# Main.net
KiCad netlist of a schematic drawn in Altium Designer
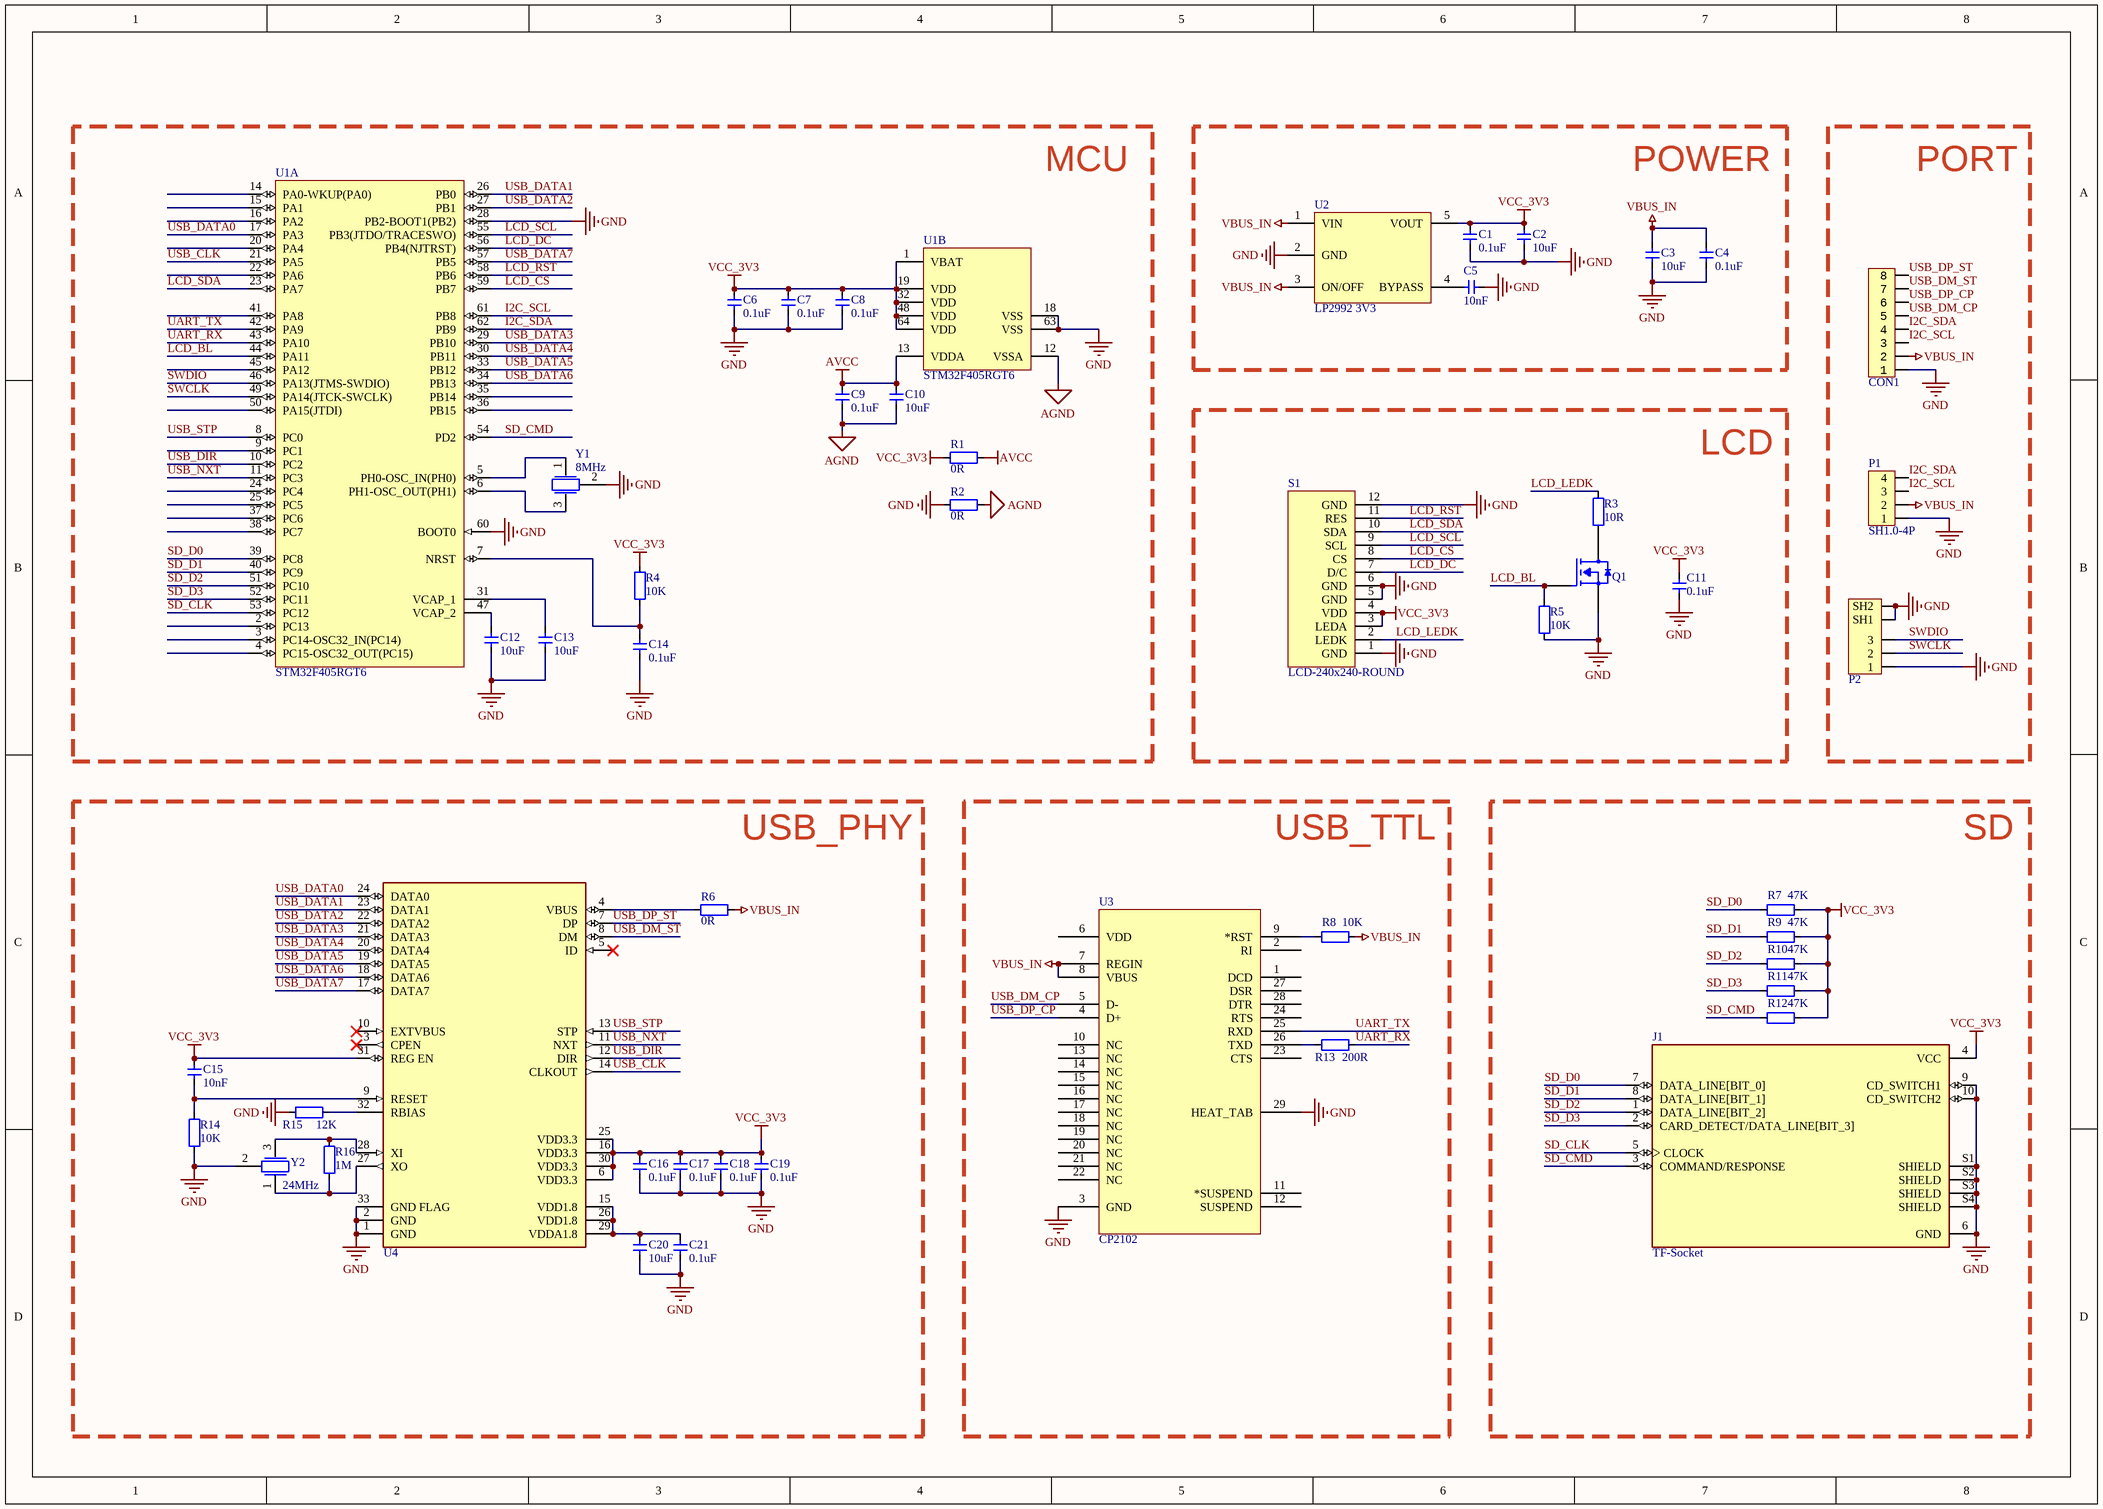
[diagram p0: Main.SchDoc]

(export (version "E")
  (design (tool "Eeschema 10.0.6"))
  (components
    (comp (ref "C1")
      (value "0.1uF")
      (footprint "CAP_0402")
      (description "Capacitor")
      (libsource (lib "MyPcbLib") (part "电容-0402"))
    )
    (comp (ref "C2")
      (value "10uF")
      (footprint "CAP_0402")
      (description "Capacitor")
      (libsource (lib "MyPcbLib") (part "电容-0402"))
    )
    (comp (ref "C3")
      (value "10uF")
      (footprint "CAP_0402")
      (description "Capacitor")
      (libsource (lib "MyPcbLib") (part "电容-0402"))
    )
    (comp (ref "C4")
      (value "0.1uF")
      (footprint "CAP_0402")
      (description "Capacitor")
      (libsource (lib "MyPcbLib") (part "电容-0402"))
    )
    (comp (ref "C5")
      (value "10nF")
      (footprint "CAP_0402")
      (description "Capacitor")
      (libsource (lib "MyPcbLib") (part "电容-0402"))
    )
    (comp (ref "C6")
      (value "0.1uF")
      (footprint "CAP_0402")
      (description "Capacitor")
      (libsource (lib "MyPcbLib") (part "电容-0402"))
    )
    (comp (ref "C7")
      (value "0.1uF")
      (footprint "CAP_0402")
      (description "Capacitor")
      (libsource (lib "MyPcbLib") (part "电容-0402"))
    )
    (comp (ref "C8")
      (value "0.1uF")
      (footprint "CAP_0402")
      (description "Capacitor")
      (libsource (lib "MyPcbLib") (part "电容-0402"))
    )
    (comp (ref "C9")
      (value "0.1uF")
      (footprint "CAP_0402")
      (description "Capacitor")
      (libsource (lib "MyPcbLib") (part "电容-0402"))
    )
    (comp (ref "C10")
      (value "10uF")
      (footprint "CAP_0402")
      (description "Capacitor")
      (libsource (lib "MyPcbLib") (part "电容-0402"))
    )
    (comp (ref "C11")
      (value "0.1uF")
      (footprint "CAP_0402")
      (description "Capacitor")
      (libsource (lib "MyPcbLib") (part "电容-0402"))
    )
    (comp (ref "C12")
      (value "10uF")
      (footprint "CAP_0402")
      (description "Capacitor")
      (libsource (lib "MyPcbLib") (part "电容-0402"))
    )
    (comp (ref "C13")
      (value "10uF")
      (footprint "CAP_0402")
      (description "Capacitor")
      (libsource (lib "MyPcbLib") (part "电容-0402"))
    )
    (comp (ref "C14")
      (value "0.1uF")
      (footprint "CAP_0402")
      (description "Capacitor")
      (libsource (lib "MyPcbLib") (part "电容-0402"))
    )
    (comp (ref "C15")
      (value "10nF")
      (footprint "CAP_0402")
      (description "Capacitor")
      (libsource (lib "MyPcbLib") (part "电容-0402"))
    )
    (comp (ref "C16")
      (value "0.1uF")
      (footprint "CAP_0402")
      (description "Capacitor")
      (libsource (lib "MyPcbLib") (part "电容-0402"))
    )
    (comp (ref "C17")
      (value "0.1uF")
      (footprint "CAP_0402")
      (description "Capacitor")
      (libsource (lib "MyPcbLib") (part "电容-0402"))
    )
    (comp (ref "C18")
      (value "0.1uF")
      (footprint "CAP_0402")
      (description "Capacitor")
      (libsource (lib "MyPcbLib") (part "电容-0402"))
    )
    (comp (ref "C19")
      (value "0.1uF")
      (footprint "CAP_0402")
      (description "Capacitor")
      (libsource (lib "MyPcbLib") (part "电容-0402"))
    )
    (comp (ref "C20")
      (value "10uF")
      (footprint "CAP_0402")
      (description "Capacitor")
      (libsource (lib "MyPcbLib") (part "电容-0402"))
    )
    (comp (ref "C21")
      (value "0.1uF")
      (footprint "CAP_0402")
      (description "Capacitor")
      (libsource (lib "MyPcbLib") (part "电容-0402"))
    )
    (comp (ref "CON1")
      (value "FFC_0.5_8")
      (footprint "FFC_0.5_8")
      (description "FFC")
      (libsource (lib "KitSprout") (part "FFC_0.5_8"))
    )
    (comp (ref "J1")
      (value "TF-Socket")
      (footprint "TF-Card-Amphenol with TF")
      (description "10 _8 + 2_ Position Card Connector Secure Digital - microSDâ„¢ Surface Mount, Right Angle Gold")
      (fields (field (name "MP") "1140084168") (field (name "MF") "Amphenol Commercial Products"))
      (libsource (lib "MyPcbLib") (part "TF-Socket"))
    )
    (comp (ref "P1") (value "SH1.0-4P") (footprint "SH1.0-4P") (libsource (lib "MyPcbLib") (part "SH1.0-4P")))
    (comp (ref "P2")
      (value "SH1.0-3P-STAND")
      (footprint "SH1.0-3P-STAND")
      (description "Header")
      (libsource (lib "MyPcbLib") (part "SH1.0-3P-STAND"))
    )
    (comp (ref "Q1")
      (value "AO3400A")
      (footprint "SOT23-3")
      (description "N-MOS")
      (libsource (lib "MyPcbLib") (part "AO3400A"))
    )
    (comp (ref "R1")
      (value "0R")
      (footprint "RES_0402")
      (description "Resistor")
      (libsource (lib "MyPcbLib") (part "电阻-0402"))
    )
    (comp (ref "R2")
      (value "0R")
      (footprint "RES_0402")
      (description "Resistor")
      (libsource (lib "MyPcbLib") (part "电阻-0402"))
    )
    (comp (ref "R3")
      (value "10R")
      (footprint "RES_0402")
      (description "Resistor")
      (libsource (lib "") (part "电阻-0402_2"))
    )
    (comp (ref "R4")
      (value "10K")
      (footprint "RES_0402")
      (description "Resistor")
      (libsource (lib "") (part "电阻-0402_2"))
    )
    (comp (ref "R5")
      (value "10K")
      (footprint "RES_0402")
      (description "Resistor")
      (libsource (lib "") (part "电阻-0402_2"))
    )
    (comp (ref "R6")
      (value "0R")
      (footprint "RES_0402")
      (description "Resistor")
      (libsource (lib "MyPcbLib") (part "电阻-0402"))
    )
    (comp (ref "R7")
      (value "47K")
      (footprint "RES_0402")
      (description "Resistor")
      (libsource (lib "MyPcbLib") (part "电阻-0402"))
    )
    (comp (ref "R8")
      (value "10K")
      (footprint "RES_0402")
      (description "Resistor")
      (libsource (lib "MyPcbLib") (part "电阻-0402"))
    )
    (comp (ref "R9")
      (value "47K")
      (footprint "RES_0402")
      (description "Resistor")
      (libsource (lib "MyPcbLib") (part "电阻-0402"))
    )
    (comp (ref "R10")
      (value "47K")
      (footprint "RES_0402")
      (description "Resistor")
      (libsource (lib "MyPcbLib") (part "电阻-0402"))
    )
    (comp (ref "R11")
      (value "47K")
      (footprint "RES_0402")
      (description "Resistor")
      (libsource (lib "MyPcbLib") (part "电阻-0402"))
    )
    (comp (ref "R12")
      (value "47K")
      (footprint "RES_0402")
      (description "Resistor")
      (libsource (lib "MyPcbLib") (part "电阻-0402"))
    )
    (comp (ref "R13")
      (value "200R")
      (footprint "RES_0402")
      (description "Resistor")
      (libsource (lib "MyPcbLib") (part "电阻-0402"))
    )
    (comp (ref "R14")
      (value "10K")
      (footprint "RES_0402")
      (description "Resistor")
      (libsource (lib "") (part "电阻-0402_1"))
    )
    (comp (ref "R15")
      (value "12K")
      (footprint "RES_0402")
      (description "Resistor")
      (libsource (lib "MyPcbLib") (part "电阻-0402"))
    )
    (comp (ref "R16")
      (value "1M")
      (footprint "RES_0402")
      (description "Resistor")
      (libsource (lib "") (part "电阻-0402_1"))
    )
    (comp (ref "S1")
      (value "LCD-240x240-ROUND")
      (footprint "LCD-240x240-ROUND")
      (description "显示屏")
      (libsource (lib "mLib") (part "LCD-240x240-ROUND"))
    )
    (comp (ref "U1")
      (value "STM32F405RGT6")
      (footprint "LQFP-64_N")
      (fields (field (name "MANUFACTURER") "STMicroelectronics"))
      (libsource (lib "STMicroelectronics STM32 F4") (part "STM32F405RGT6"))
    )
    (comp (ref "U2")
      (value "LP2992 3V3")
      (footprint "SOT23-5")
      (description "LDO")
      (libsource (lib "MyPcbLib") (part "LP2992"))
    )
    (comp (ref "U3")
      (value "CP2102")
      (footprint "QFN-28")
      (description "USB转TTL")
      (libsource (lib "mLib") (part "CP2102"))
    )
    (comp (ref "U4")
      (value "USB3300-EZK-TR")
      (footprint "QFN-32")
      (libsource (lib "mLib") (part "USB3300-EZK-TR"))
    )
    (comp (ref "Y1")
      (value "8MHz")
      (footprint "晶振-3P")
      (description "村田贴片")
      (libsource (lib "MyPcbLib") (part "晶振-3Pin"))
    )
    (comp (ref "Y2")
      (value "24MHz")
      (footprint "晶振-3P")
      (description "村田贴片")
      (libsource (lib "MyPcbLib") (part "晶振-3Pin"))
    )
  )
  (nets
    (net (code "1") (name "/I2C_SCL") (class "Default")
      (node (ref "CON1") (pin "3") (pinfunction "3_3") (pintype "passive"))
      (node (ref "P1") (pin "3") (pinfunction "3_3") (pintype "passive"))
      (node (ref "U1") (pin "61") (pinfunction "PB8_61") (pintype "bidirectional"))
    )
    (net (code "2") (name "/I2C_SDA") (class "Default")
      (node (ref "CON1") (pin "4") (pinfunction "4_4") (pintype "passive"))
      (node (ref "P1") (pin "4") (pinfunction "4_4") (pintype "passive"))
      (node (ref "U1") (pin "62") (pinfunction "PB9_62") (pintype "bidirectional"))
    )
    (net (code "3") (name "/LCD_BL") (class "Default")
      (node (ref "Q1") (pin "1") (pinfunction "G_1") (pintype "passive"))
      (node (ref "R5") (pin "2") (pinfunction "2_2") (pintype "passive"))
      (node (ref "U1") (pin "44") (pinfunction "PA11_44") (pintype "bidirectional"))
    )
    (net (code "4") (name "/LCD_CS") (class "Default")
      (node (ref "S1") (pin "8") (pinfunction "CS_8") (pintype "passive"))
      (node (ref "U1") (pin "59") (pinfunction "PB7_59") (pintype "bidirectional"))
    )
    (net (code "5") (name "/LCD_DC") (class "Default")
      (node (ref "S1") (pin "7") (pinfunction "D/C_7") (pintype "passive"))
      (node (ref "U1") (pin "56") (pinfunction "PB4(NJTRST)_56") (pintype "bidirectional"))
    )
    (net (code "6") (name "/LCD_LEDK") (class "Default")
      (node (ref "R3") (pin "2") (pinfunction "2_2") (pintype "passive"))
      (node (ref "S1") (pin "2") (pinfunction "LEDK_2") (pintype "passive"))
    )
    (net (code "7") (name "/LCD_RST") (class "Default")
      (node (ref "S1") (pin "11") (pinfunction "RES_11") (pintype "passive"))
      (node (ref "U1") (pin "58") (pinfunction "PB6_58") (pintype "bidirectional"))
    )
    (net (code "8") (name "/LCD_SCL") (class "Default")
      (node (ref "S1") (pin "9") (pinfunction "SCL_9") (pintype "passive"))
      (node (ref "U1") (pin "55") (pinfunction "PB3(JTDO/TRACESWO)_55") (pintype "bidirectional"))
    )
    (net (code "9") (name "/LCD_SDA") (class "Default")
      (node (ref "S1") (pin "10") (pinfunction "SDA_10") (pintype "passive"))
      (node (ref "U1") (pin "23") (pinfunction "PA7_23") (pintype "bidirectional"))
    )
    (net (code "10") (name "/SD_CLK") (class "Default")
      (node (ref "J1") (pin "5") (pinfunction "CLOCK_5") (pintype "bidirectional"))
      (node (ref "U1") (pin "53") (pinfunction "PC12_53") (pintype "bidirectional"))
    )
    (net (code "11") (name "/SD_CMD") (class "Default")
      (node (ref "J1") (pin "3") (pinfunction "COMMAND/RESPONSE_3") (pintype "bidirectional"))
      (node (ref "R12") (pin "2") (pinfunction "2_2") (pintype "passive"))
      (node (ref "U1") (pin "54") (pinfunction "PD2_54") (pintype "bidirectional"))
    )
    (net (code "12") (name "/SD_D0") (class "Default")
      (node (ref "J1") (pin "7") (pinfunction "DATA_LINE[BIT_0]_7") (pintype "bidirectional"))
      (node (ref "R7") (pin "2") (pinfunction "2_2") (pintype "passive"))
      (node (ref "U1") (pin "39") (pinfunction "PC8_39") (pintype "bidirectional"))
    )
    (net (code "13") (name "/SD_D1") (class "Default")
      (node (ref "J1") (pin "8") (pinfunction "DATA_LINE[BIT_1]_8") (pintype "bidirectional"))
      (node (ref "R9") (pin "2") (pinfunction "2_2") (pintype "passive"))
      (node (ref "U1") (pin "40") (pinfunction "PC9_40") (pintype "bidirectional"))
    )
    (net (code "14") (name "/SD_D2") (class "Default")
      (node (ref "J1") (pin "1") (pinfunction "DATA_LINE[BIT_2]_1") (pintype "bidirectional"))
      (node (ref "R10") (pin "2") (pinfunction "2_2") (pintype "passive"))
      (node (ref "U1") (pin "51") (pinfunction "PC10_51") (pintype "bidirectional"))
    )
    (net (code "15") (name "/SD_D3") (class "Default")
      (node (ref "J1") (pin "2") (pinfunction "CARD_DETECT/DATA_LINE[BIT_3]_2") (pintype "bidirectional"))
      (node (ref "R11") (pin "2") (pinfunction "2_2") (pintype "passive"))
      (node (ref "U1") (pin "52") (pinfunction "PC11_52") (pintype "bidirectional"))
    )
    (net (code "16") (name "/SWCLK") (class "Default")
      (node (ref "P2") (pin "2") (pinfunction "2_2") (pintype "passive"))
      (node (ref "U1") (pin "49") (pinfunction "PA14(JTCK-SWCLK)_49") (pintype "bidirectional"))
    )
    (net (code "17") (name "/SWDIO") (class "Default")
      (node (ref "P2") (pin "3") (pinfunction "3_3") (pintype "passive"))
      (node (ref "U1") (pin "46") (pinfunction "PA13(JTMS-SWDIO)_46") (pintype "bidirectional"))
    )
    (net (code "18") (name "/UART_RX") (class "Default")
      (node (ref "R13") (pin "1") (pinfunction "1_1") (pintype "passive"))
      (node (ref "U1") (pin "43") (pinfunction "PA10_43") (pintype "bidirectional"))
    )
    (net (code "19") (name "/UART_TX") (class "Default")
      (node (ref "U1") (pin "42") (pinfunction "PA9_42") (pintype "bidirectional"))
      (node (ref "U3") (pin "25") (pinfunction "RXD_25") (pintype "passive"))
    )
    (net (code "20") (name "/USB_CLK") (class "Default")
      (node (ref "U1") (pin "21") (pinfunction "PA5_21") (pintype "bidirectional"))
      (node (ref "U4") (pin "14") (pinfunction "CLKOUT_14") (pintype "output"))
    )
    (net (code "21") (name "/USB_DATA0") (class "Default")
      (node (ref "U1") (pin "17") (pinfunction "PA3_17") (pintype "bidirectional"))
      (node (ref "U4") (pin "24") (pinfunction "DATA0_24") (pintype "bidirectional"))
    )
    (net (code "22") (name "/USB_DATA1") (class "Default")
      (node (ref "U1") (pin "26") (pinfunction "PB0_26") (pintype "bidirectional"))
      (node (ref "U4") (pin "23") (pinfunction "DATA1_23") (pintype "bidirectional"))
    )
    (net (code "23") (name "/USB_DATA2") (class "Default")
      (node (ref "U1") (pin "27") (pinfunction "PB1_27") (pintype "bidirectional"))
      (node (ref "U4") (pin "22") (pinfunction "DATA2_22") (pintype "bidirectional"))
    )
    (net (code "24") (name "/USB_DATA3") (class "Default")
      (node (ref "U1") (pin "29") (pinfunction "PB10_29") (pintype "bidirectional"))
      (node (ref "U4") (pin "21") (pinfunction "DATA3_21") (pintype "bidirectional"))
    )
    (net (code "25") (name "/USB_DATA4") (class "Default")
      (node (ref "U1") (pin "30") (pinfunction "PB11_30") (pintype "bidirectional"))
      (node (ref "U4") (pin "20") (pinfunction "DATA4_20") (pintype "bidirectional"))
    )
    (net (code "26") (name "/USB_DATA5") (class "Default")
      (node (ref "U1") (pin "33") (pinfunction "PB12_33") (pintype "bidirectional"))
      (node (ref "U4") (pin "19") (pinfunction "DATA5_19") (pintype "bidirectional"))
    )
    (net (code "27") (name "/USB_DATA6") (class "Default")
      (node (ref "U1") (pin "34") (pinfunction "PB13_34") (pintype "bidirectional"))
      (node (ref "U4") (pin "18") (pinfunction "DATA6_18") (pintype "bidirectional"))
    )
    (net (code "28") (name "/USB_DATA7") (class "Default")
      (node (ref "U1") (pin "57") (pinfunction "PB5_57") (pintype "bidirectional"))
      (node (ref "U4") (pin "17") (pinfunction "DATA7_17") (pintype "bidirectional"))
    )
    (net (code "29") (name "/USB_DIR") (class "Default")
      (node (ref "U1") (pin "10") (pinfunction "PC2_10") (pintype "bidirectional"))
      (node (ref "U4") (pin "12") (pinfunction "DIR_12") (pintype "output"))
    )
    (net (code "30") (name "/USB_DM_CP") (class "Default")
      (node (ref "CON1") (pin "5") (pinfunction "5_5") (pintype "passive"))
      (node (ref "U3") (pin "5") (pinfunction "D-_5") (pintype "passive"))
    )
    (net (code "31") (name "/USB_DM_ST") (class "Default")
      (node (ref "CON1") (pin "7") (pinfunction "7_7") (pintype "passive"))
      (node (ref "U4") (pin "8") (pinfunction "DM_8") (pintype "bidirectional"))
    )
    (net (code "32") (name "/USB_DP_CP") (class "Default")
      (node (ref "CON1") (pin "6") (pinfunction "6_6") (pintype "passive"))
      (node (ref "U3") (pin "4") (pinfunction "D+_4") (pintype "passive"))
    )
    (net (code "33") (name "/USB_DP_ST") (class "Default")
      (node (ref "CON1") (pin "8") (pinfunction "8_8") (pintype "passive"))
      (node (ref "U4") (pin "7") (pinfunction "DP_7") (pintype "bidirectional"))
    )
    (net (code "34") (name "/USB_NXT") (class "Default")
      (node (ref "U1") (pin "11") (pinfunction "PC3_11") (pintype "bidirectional"))
      (node (ref "U4") (pin "11") (pinfunction "NXT_11") (pintype "output"))
    )
    (net (code "35") (name "/USB_STP") (class "Default")
      (node (ref "U1") (pin "8") (pinfunction "PC0_8") (pintype "bidirectional"))
      (node (ref "U4") (pin "13") (pinfunction "STP_13") (pintype "input"))
    )
    (net (code "36") (name "AGND") (class "Default")
      (node (ref "C10") (pin "1") (pinfunction "1_1") (pintype "passive"))
      (node (ref "C9") (pin "1") (pinfunction "1_1") (pintype "passive"))
      (node (ref "R2") (pin "1") (pinfunction "1_1") (pintype "passive"))
      (node (ref "U1") (pin "12") (pinfunction "VSSA_12") (pintype "power_in"))
    )
    (net (code "37") (name "AVCC") (class "Default")
      (node (ref "C10") (pin "2") (pinfunction "2_2") (pintype "passive"))
      (node (ref "C9") (pin "2") (pinfunction "2_2") (pintype "passive"))
      (node (ref "R1") (pin "1") (pinfunction "1_1") (pintype "passive"))
      (node (ref "U1") (pin "13") (pinfunction "VDDA_13") (pintype "power_in"))
    )
    (net (code "38") (name "GND") (class "Default")
      (node (ref "C1") (pin "1") (pinfunction "1_1") (pintype "passive"))
      (node (ref "C11") (pin "1") (pinfunction "1_1") (pintype "passive"))
      (node (ref "C12") (pin "1") (pinfunction "1_1") (pintype "passive"))
      (node (ref "C13") (pin "1") (pinfunction "1_1") (pintype "passive"))
      (node (ref "C14") (pin "1") (pinfunction "1_1") (pintype "passive"))
      (node (ref "C16") (pin "2") (pinfunction "2_2") (pintype "passive"))
      (node (ref "C17") (pin "2") (pinfunction "2_2") (pintype "passive"))
      (node (ref "C18") (pin "2") (pinfunction "2_2") (pintype "passive"))
      (node (ref "C19") (pin "2") (pinfunction "2_2") (pintype "passive"))
      (node (ref "C2") (pin "1") (pinfunction "1_1") (pintype "passive"))
      (node (ref "C20") (pin "2") (pinfunction "2_2") (pintype "passive"))
      (node (ref "C21") (pin "2") (pinfunction "2_2") (pintype "passive"))
      (node (ref "C3") (pin "1") (pinfunction "1_1") (pintype "passive"))
      (node (ref "C4") (pin "1") (pinfunction "1_1") (pintype "passive"))
      (node (ref "C5") (pin "1") (pinfunction "1_1") (pintype "passive"))
      (node (ref "C6") (pin "1") (pinfunction "1_1") (pintype "passive"))
      (node (ref "C7") (pin "1") (pinfunction "1_1") (pintype "passive"))
      (node (ref "C8") (pin "1") (pinfunction "1_1") (pintype "passive"))
      (node (ref "CON1") (pin "1") (pinfunction "1_1") (pintype "passive"))
      (node (ref "J1") (pin "10") (pinfunction "CD_SWITCH2_10") (pintype "bidirectional"))
      (node (ref "J1") (pin "6") (pinfunction "GND_6") (pintype "power_in"))
      (node (ref "J1") (pin "9") (pinfunction "CD_SWITCH1_9") (pintype "bidirectional"))
      (node (ref "J1") (pin "S1") (pinfunction "SHIELD_S1") (pintype "passive"))
      (node (ref "J1") (pin "S2") (pinfunction "SHIELD_S2") (pintype "passive"))
      (node (ref "J1") (pin "S3") (pinfunction "SHIELD_S3") (pintype "passive"))
      (node (ref "J1") (pin "S4") (pinfunction "SHIELD_S4") (pintype "passive"))
      (node (ref "P1") (pin "1") (pinfunction "1_1") (pintype "passive"))
      (node (ref "P2") (pin "1") (pinfunction "1_1") (pintype "passive"))
      (node (ref "P2") (pin "SH1") (pinfunction "SH1_SH1") (pintype "passive"))
      (node (ref "P2") (pin "SH2") (pinfunction "SH2_SH2") (pintype "passive"))
      (node (ref "Q1") (pin "2") (pinfunction "S_2") (pintype "passive"))
      (node (ref "R14") (pin "2") (pinfunction "2_2") (pintype "passive"))
      (node (ref "R15") (pin "2") (pinfunction "2_2") (pintype "passive"))
      (node (ref "R2") (pin "2") (pinfunction "2_2") (pintype "passive"))
      (node (ref "R5") (pin "1") (pinfunction "1_1") (pintype "passive"))
      (node (ref "S1") (pin "1") (pinfunction "GND_1") (pintype "passive"))
      (node (ref "S1") (pin "12") (pinfunction "GND_12") (pintype "passive"))
      (node (ref "S1") (pin "5") (pinfunction "GND_5") (pintype "passive"))
      (node (ref "S1") (pin "6") (pinfunction "GND_6") (pintype "passive"))
      (node (ref "U1") (pin "18") (pinfunction "VSS_18") (pintype "power_in"))
      (node (ref "U1") (pin "28") (pinfunction "PB2-BOOT1(PB2)_28") (pintype "bidirectional"))
      (node (ref "U1") (pin "60") (pinfunction "BOOT0_60") (pintype "input"))
      (node (ref "U1") (pin "63") (pinfunction "VSS_63") (pintype "power_in"))
      (node (ref "U2") (pin "2") (pinfunction "GND_2") (pintype "passive"))
      (node (ref "U3") (pin "29") (pinfunction "HEAT_TAB_29") (pintype "passive"))
      (node (ref "U3") (pin "3") (pinfunction "GND_3") (pintype "passive"))
      (node (ref "U4") (pin "1") (pinfunction "GND_1") (pintype "power_in"))
      (node (ref "U4") (pin "2") (pinfunction "GND_2") (pintype "power_in"))
      (node (ref "U4") (pin "33") (pinfunction "GND_FLAG_33") (pintype "power_in"))
      (node (ref "Y1") (pin "2") (pinfunction "2_2") (pintype "passive"))
      (node (ref "Y2") (pin "2") (pinfunction "2_2") (pintype "passive"))
    )
    (net (code "39") (name "Net-(Q1-D)") (class "Default")
      (node (ref "Q1") (pin "3") (pinfunction "D_3") (pintype "passive"))
      (node (ref "R3") (pin "1") (pinfunction "1_1") (pintype "passive"))
    )
    (net (code "40") (name "Net-(U1A-NRST)") (class "Default")
      (node (ref "C14") (pin "2") (pinfunction "2_2") (pintype "passive"))
      (node (ref "R4") (pin "1") (pinfunction "1_1") (pintype "passive"))
      (node (ref "U1") (pin "7") (pinfunction "NRST_7") (pintype "bidirectional"))
    )
    (net (code "41") (name "Net-(U1A-PH0-OSC_IN(PH0))") (class "Default")
      (node (ref "U1") (pin "5") (pinfunction "PH0-OSC_IN(PH0)_5") (pintype "bidirectional"))
      (node (ref "Y1") (pin "1") (pinfunction "1_1") (pintype "passive"))
    )
    (net (code "42") (name "Net-(U1A-PH1-OSC_OUT(PH1))") (class "Default")
      (node (ref "U1") (pin "6") (pinfunction "PH1-OSC_OUT(PH1)_6") (pintype "bidirectional"))
      (node (ref "Y1") (pin "3") (pinfunction "3_3") (pintype "passive"))
    )
    (net (code "43") (name "Net-(U1A-VCAP_1)") (class "Default")
      (node (ref "C13") (pin "2") (pinfunction "2_2") (pintype "passive"))
      (node (ref "U1") (pin "31") (pinfunction "VCAP_1_31") (pintype "power_in"))
    )
    (net (code "44") (name "Net-(U1A-VCAP_2)") (class "Default")
      (node (ref "C12") (pin "2") (pinfunction "2_2") (pintype "passive"))
      (node (ref "U1") (pin "47") (pinfunction "VCAP_2_47") (pintype "power_in"))
    )
    (net (code "45") (name "Net-(U2-BYPASS)") (class "Default")
      (node (ref "C5") (pin "2") (pinfunction "2_2") (pintype "passive"))
      (node (ref "U2") (pin "4") (pinfunction "BYPASS_4") (pintype "passive"))
    )
    (net (code "46") (name "Net-(U3-*RST)") (class "Default")
      (node (ref "R8") (pin "2") (pinfunction "2_2") (pintype "passive"))
      (node (ref "U3") (pin "9") (pinfunction "*RST_9") (pintype "passive"))
    )
    (net (code "47") (name "Net-(U3-TXD)") (class "Default")
      (node (ref "R13") (pin "2") (pinfunction "2_2") (pintype "passive"))
      (node (ref "U3") (pin "26") (pinfunction "TXD_26") (pintype "passive"))
    )
    (net (code "48") (name "Net-(U4-RBIAS)") (class "Default")
      (node (ref "R15") (pin "1") (pinfunction "1_1") (pintype "passive"))
      (node (ref "U4") (pin "32") (pinfunction "RBIAS_32") (pintype "power_in"))
    )
    (net (code "49") (name "Net-(U4-RESET)") (class "Default")
      (node (ref "C15") (pin "2") (pinfunction "2_2") (pintype "passive"))
      (node (ref "R14") (pin "1") (pinfunction "1_1") (pintype "passive"))
      (node (ref "U4") (pin "9") (pinfunction "RESET_9") (pintype "input"))
    )
    (net (code "50") (name "Net-(U4-VBUS)") (class "Default")
      (node (ref "R6") (pin "2") (pinfunction "2_2") (pintype "passive"))
      (node (ref "U4") (pin "4") (pinfunction "VBUS_4") (pintype "bidirectional"))
    )
    (net (code "51") (name "Net-(U4-VDDA1.8)") (class "Default")
      (node (ref "C20") (pin "1") (pinfunction "1_1") (pintype "passive"))
      (node (ref "C21") (pin "1") (pinfunction "1_1") (pintype "passive"))
      (node (ref "U4") (pin "15") (pinfunction "VDD1.8_15") (pintype "power_in"))
      (node (ref "U4") (pin "26") (pinfunction "VDD1.8_26") (pintype "power_in"))
      (node (ref "U4") (pin "29") (pinfunction "VDDA1.8_29") (pintype "power_in"))
    )
    (net (code "52") (name "Net-(U4-XI)") (class "Default")
      (node (ref "R16") (pin "1") (pinfunction "1_1") (pintype "passive"))
      (node (ref "U4") (pin "28") (pinfunction "XI_28") (pintype "input"))
      (node (ref "Y2") (pin "3") (pinfunction "3_3") (pintype "passive"))
    )
    (net (code "53") (name "Net-(U4-XO)") (class "Default")
      (node (ref "R16") (pin "2") (pinfunction "2_2") (pintype "passive"))
      (node (ref "U4") (pin "27") (pinfunction "XO_27") (pintype "output"))
      (node (ref "Y2") (pin "1") (pinfunction "1_1") (pintype "passive"))
    )
    (net (code "54") (name "VBUS_IN") (class "Default")
      (node (ref "C3") (pin "2") (pinfunction "2_2") (pintype "passive"))
      (node (ref "C4") (pin "2") (pinfunction "2_2") (pintype "passive"))
      (node (ref "CON1") (pin "2") (pinfunction "2_2") (pintype "passive"))
      (node (ref "P1") (pin "2") (pinfunction "2_2") (pintype "passive"))
      (node (ref "R6") (pin "1") (pinfunction "1_1") (pintype "passive"))
      (node (ref "R8") (pin "1") (pinfunction "1_1") (pintype "passive"))
      (node (ref "U2") (pin "1") (pinfunction "VIN_1") (pintype "passive"))
      (node (ref "U2") (pin "3") (pinfunction "ON/OFF_3") (pintype "passive"))
      (node (ref "U3") (pin "7") (pinfunction "REGIN_7") (pintype "passive"))
      (node (ref "U3") (pin "8") (pinfunction "VBUS_8") (pintype "passive"))
    )
    (net (code "55") (name "VCC_3V3") (class "Default")
      (node (ref "C1") (pin "2") (pinfunction "2_2") (pintype "passive"))
      (node (ref "C11") (pin "2") (pinfunction "2_2") (pintype "passive"))
      (node (ref "C15") (pin "1") (pinfunction "1_1") (pintype "passive"))
      (node (ref "C16") (pin "1") (pinfunction "1_1") (pintype "passive"))
      (node (ref "C17") (pin "1") (pinfunction "1_1") (pintype "passive"))
      (node (ref "C18") (pin "1") (pinfunction "1_1") (pintype "passive"))
      (node (ref "C19") (pin "1") (pinfunction "1_1") (pintype "passive"))
      (node (ref "C2") (pin "2") (pinfunction "2_2") (pintype "passive"))
      (node (ref "C6") (pin "2") (pinfunction "2_2") (pintype "passive"))
      (node (ref "C7") (pin "2") (pinfunction "2_2") (pintype "passive"))
      (node (ref "C8") (pin "2") (pinfunction "2_2") (pintype "passive"))
      (node (ref "J1") (pin "4") (pinfunction "VCC_4") (pintype "power_in"))
      (node (ref "R1") (pin "2") (pinfunction "2_2") (pintype "passive"))
      (node (ref "R10") (pin "1") (pinfunction "1_1") (pintype "passive"))
      (node (ref "R11") (pin "1") (pinfunction "1_1") (pintype "passive"))
      (node (ref "R12") (pin "1") (pinfunction "1_1") (pintype "passive"))
      (node (ref "R4") (pin "2") (pinfunction "2_2") (pintype "passive"))
      (node (ref "R7") (pin "1") (pinfunction "1_1") (pintype "passive"))
      (node (ref "R9") (pin "1") (pinfunction "1_1") (pintype "passive"))
      (node (ref "S1") (pin "3") (pinfunction "LEDA_3") (pintype "passive"))
      (node (ref "S1") (pin "4") (pinfunction "VDD_4") (pintype "passive"))
      (node (ref "U1") (pin "1") (pinfunction "VBAT_1") (pintype "power_in"))
      (node (ref "U1") (pin "19") (pinfunction "VDD_19") (pintype "power_in"))
      (node (ref "U1") (pin "32") (pinfunction "VDD_32") (pintype "power_in"))
      (node (ref "U1") (pin "48") (pinfunction "VDD_48") (pintype "power_in"))
      (node (ref "U1") (pin "64") (pinfunction "VDD_64") (pintype "power_in"))
      (node (ref "U2") (pin "5") (pinfunction "VOUT_5") (pintype "passive"))
      (node (ref "U4") (pin "16") (pinfunction "VDD3.3_16") (pintype "power_in"))
      (node (ref "U4") (pin "25") (pinfunction "VDD3.3_25") (pintype "power_in"))
      (node (ref "U4") (pin "30") (pinfunction "VDD3.3_30") (pintype "power_in"))
      (node (ref "U4") (pin "31") (pinfunction "REG_EN_31") (pintype "bidirectional"))
      (node (ref "U4") (pin "6") (pinfunction "VDD3.3_6") (pintype "power_in"))
    )
    (net (code "56") (name "unconnected-(U1A-PA0-WKUP(PA0)-Pad14)") (class "Default")
      (node (ref "U1") (pin "14") (pinfunction "PA0-WKUP(PA0)_14") (pintype "bidirectional"))
    )
    (net (code "57") (name "unconnected-(U1A-PA1-Pad15)") (class "Default")
      (node (ref "U1") (pin "15") (pinfunction "PA1_15") (pintype "bidirectional"))
    )
    (net (code "58") (name "unconnected-(U1A-PA2-Pad16)") (class "Default")
      (node (ref "U1") (pin "16") (pinfunction "PA2_16") (pintype "bidirectional"))
    )
    (net (code "59") (name "unconnected-(U1A-PA4-Pad20)") (class "Default")
      (node (ref "U1") (pin "20") (pinfunction "PA4_20") (pintype "bidirectional"))
    )
    (net (code "60") (name "unconnected-(U1A-PA6-Pad22)") (class "Default")
      (node (ref "U1") (pin "22") (pinfunction "PA6_22") (pintype "bidirectional"))
    )
    (net (code "61") (name "unconnected-(U1A-PA8-Pad41)") (class "Default")
      (node (ref "U1") (pin "41") (pinfunction "PA8_41") (pintype "bidirectional"))
    )
    (net (code "62") (name "unconnected-(U1A-PA12-Pad45)") (class "Default")
      (node (ref "U1") (pin "45") (pinfunction "PA12_45") (pintype "bidirectional"))
    )
    (net (code "63") (name "unconnected-(U1A-PA15(JTDI)-Pad50)") (class "Default")
      (node (ref "U1") (pin "50") (pinfunction "PA15(JTDI)_50") (pintype "bidirectional"))
    )
    (net (code "64") (name "unconnected-(U1A-PB14-Pad35)") (class "Default")
      (node (ref "U1") (pin "35") (pinfunction "PB14_35") (pintype "bidirectional"))
    )
    (net (code "65") (name "unconnected-(U1A-PB15-Pad36)") (class "Default")
      (node (ref "U1") (pin "36") (pinfunction "PB15_36") (pintype "bidirectional"))
    )
    (net (code "66") (name "unconnected-(U1A-PC1-Pad9)") (class "Default")
      (node (ref "U1") (pin "9") (pinfunction "PC1_9") (pintype "bidirectional"))
    )
    (net (code "67") (name "unconnected-(U1A-PC4-Pad24)") (class "Default")
      (node (ref "U1") (pin "24") (pinfunction "PC4_24") (pintype "bidirectional"))
    )
    (net (code "68") (name "unconnected-(U1A-PC5-Pad25)") (class "Default")
      (node (ref "U1") (pin "25") (pinfunction "PC5_25") (pintype "bidirectional"))
    )
    (net (code "69") (name "unconnected-(U1A-PC6-Pad37)") (class "Default")
      (node (ref "U1") (pin "37") (pinfunction "PC6_37") (pintype "bidirectional"))
    )
    (net (code "70") (name "unconnected-(U1A-PC7-Pad38)") (class "Default")
      (node (ref "U1") (pin "38") (pinfunction "PC7_38") (pintype "bidirectional"))
    )
    (net (code "71") (name "unconnected-(U1A-PC13-Pad2)") (class "Default")
      (node (ref "U1") (pin "2") (pinfunction "PC13_2") (pintype "bidirectional"))
    )
    (net (code "72") (name "unconnected-(U1A-PC14-OSC32_IN(PC14)-Pad3)") (class "Default")
      (node (ref "U1") (pin "3") (pinfunction "PC14-OSC32_IN(PC14)_3") (pintype "bidirectional"))
    )
    (net (code "73") (name "unconnected-(U1A-PC15-OSC32_OUT(PC15)-Pad4)") (class "Default")
      (node (ref "U1") (pin "4") (pinfunction "PC15-OSC32_OUT(PC15)_4") (pintype "bidirectional"))
    )
    (net (code "74") (name "unconnected-(U3-*SUSPEND-Pad11)") (class "Default")
      (node (ref "U3") (pin "11") (pinfunction "*SUSPEND_11") (pintype "passive"))
    )
    (net (code "75") (name "unconnected-(U3-CTS-Pad23)") (class "Default")
      (node (ref "U3") (pin "23") (pinfunction "CTS_23") (pintype "passive"))
    )
    (net (code "76") (name "unconnected-(U3-DCD-Pad1)") (class "Default")
      (node (ref "U3") (pin "1") (pinfunction "DCD_1") (pintype "passive"))
    )
    (net (code "77") (name "unconnected-(U3-DSR-Pad27)") (class "Default")
      (node (ref "U3") (pin "27") (pinfunction "DSR_27") (pintype "passive"))
    )
    (net (code "78") (name "unconnected-(U3-DTR-Pad28)") (class "Default")
      (node (ref "U3") (pin "28") (pinfunction "DTR_28") (pintype "passive"))
    )
    (net (code "79") (name "unconnected-(U3-NC-Pad10)") (class "Default")
      (node (ref "U3") (pin "10") (pinfunction "NC_10") (pintype "passive"))
    )
    (net (code "80") (name "unconnected-(U3-NC-Pad13)") (class "Default")
      (node (ref "U3") (pin "13") (pinfunction "NC_13") (pintype "passive"))
    )
    (net (code "81") (name "unconnected-(U3-NC-Pad14)") (class "Default")
      (node (ref "U3") (pin "14") (pinfunction "NC_14") (pintype "passive"))
    )
    (net (code "82") (name "unconnected-(U3-NC-Pad15)") (class "Default")
      (node (ref "U3") (pin "15") (pinfunction "NC_15") (pintype "passive"))
    )
    (net (code "83") (name "unconnected-(U3-NC-Pad16)") (class "Default")
      (node (ref "U3") (pin "16") (pinfunction "NC_16") (pintype "passive"))
    )
    (net (code "84") (name "unconnected-(U3-NC-Pad17)") (class "Default")
      (node (ref "U3") (pin "17") (pinfunction "NC_17") (pintype "passive"))
    )
    (net (code "85") (name "unconnected-(U3-NC-Pad18)") (class "Default")
      (node (ref "U3") (pin "18") (pinfunction "NC_18") (pintype "passive"))
    )
    (net (code "86") (name "unconnected-(U3-NC-Pad19)") (class "Default")
      (node (ref "U3") (pin "19") (pinfunction "NC_19") (pintype "passive"))
    )
    (net (code "87") (name "unconnected-(U3-NC-Pad20)") (class "Default")
      (node (ref "U3") (pin "20") (pinfunction "NC_20") (pintype "passive"))
    )
    (net (code "88") (name "unconnected-(U3-NC-Pad21)") (class "Default")
      (node (ref "U3") (pin "21") (pinfunction "NC_21") (pintype "passive"))
    )
    (net (code "89") (name "unconnected-(U3-NC-Pad22)") (class "Default")
      (node (ref "U3") (pin "22") (pinfunction "NC_22") (pintype "passive"))
    )
    (net (code "90") (name "unconnected-(U3-RI-Pad2)") (class "Default")
      (node (ref "U3") (pin "2") (pinfunction "RI_2") (pintype "passive"))
    )
    (net (code "91") (name "unconnected-(U3-RTS-Pad24)") (class "Default")
      (node (ref "U3") (pin "24") (pinfunction "RTS_24") (pintype "passive"))
    )
    (net (code "92") (name "unconnected-(U3-SUSPEND-Pad12)") (class "Default")
      (node (ref "U3") (pin "12") (pinfunction "SUSPEND_12") (pintype "passive"))
    )
    (net (code "93") (name "unconnected-(U3-VDD-Pad6)") (class "Default")
      (node (ref "U3") (pin "6") (pinfunction "VDD_6") (pintype "passive"))
    )
    (net (code "94") (name "unconnected-(U4-CPEN-Pad3)") (class "Default")
      (node (ref "U4") (pin "3") (pinfunction "CPEN_3") (pintype "output+no_connect"))
    )
    (net (code "95") (name "unconnected-(U4-EXTVBUS-Pad10)") (class "Default")
      (node (ref "U4") (pin "10") (pinfunction "EXTVBUS_10") (pintype "input+no_connect"))
    )
    (net (code "96") (name "unconnected-(U4-ID-Pad5)") (class "Default")
      (node (ref "U4") (pin "5") (pinfunction "ID_5") (pintype "input+no_connect"))
    )
  )
)
